# rev1_0.net
KiCad netlist of a schematic drawn in EAGLE
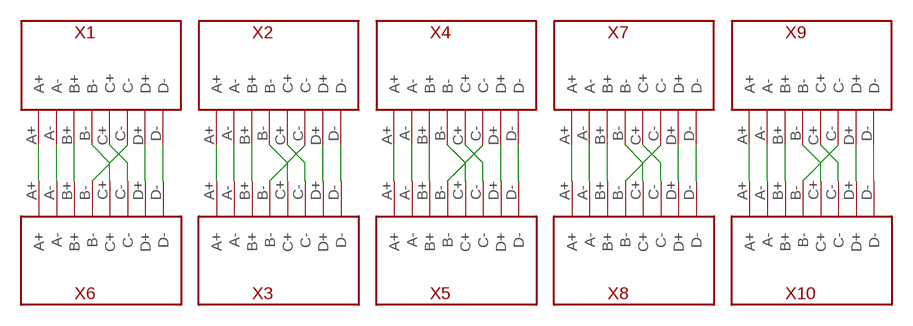
[diagram p0: schematic, sheet 1]

(export (version "E")
  (design (tool "Eeschema 10.0.6"))
  (components
    (comp (ref "X1")
      (value "ETHER_BRKOUT")
      (footprint "eagle-import:ETHER_BRKOUT")
      (libsource (lib "eagle-import") (part "ETHER_BRKOUT"))
    )
    (comp (ref "X2")
      (value "ETHER_BRKOUT")
      (footprint "eagle-import:ETHER_BRKOUT")
      (libsource (lib "eagle-import") (part "ETHER_BRKOUT"))
    )
    (comp (ref "X3")
      (value "ETHER_BRKOUT")
      (footprint "eagle-import:ETHER_BRKOUT")
      (libsource (lib "eagle-import") (part "ETHER_BRKOUT"))
    )
    (comp (ref "X4")
      (value "ETHER_BRKOUT")
      (footprint "eagle-import:ETHER_BRKOUT")
      (libsource (lib "eagle-import") (part "ETHER_BRKOUT"))
    )
    (comp (ref "X5")
      (value "ETHER_BRKOUT")
      (footprint "eagle-import:ETHER_BRKOUT")
      (libsource (lib "eagle-import") (part "ETHER_BRKOUT"))
    )
    (comp (ref "X6")
      (value "ETHER_BRKOUT")
      (footprint "eagle-import:ETHER_BRKOUT")
      (libsource (lib "eagle-import") (part "ETHER_BRKOUT"))
    )
    (comp (ref "X7")
      (value "ETHER_BRKOUT")
      (footprint "eagle-import:ETHER_BRKOUT")
      (libsource (lib "eagle-import") (part "ETHER_BRKOUT"))
    )
    (comp (ref "X8")
      (value "ETHER_BRKOUT")
      (footprint "eagle-import:ETHER_BRKOUT")
      (libsource (lib "eagle-import") (part "ETHER_BRKOUT"))
    )
    (comp (ref "X9")
      (value "ETHER_BRKOUT")
      (footprint "eagle-import:ETHER_BRKOUT")
      (libsource (lib "eagle-import") (part "ETHER_BRKOUT"))
    )
    (comp (ref "X10")
      (value "ETHER_BRKOUT")
      (footprint "eagle-import:ETHER_BRKOUT")
      (libsource (lib "eagle-import") (part "ETHER_BRKOUT"))
    )
  )
  (nets
    (net (code "1") (name "Net-(X1-PadA+)") (class "Default")
      (node (ref "X1") (pin "A+") (pinfunction "A+_A+") (pintype "bidirectional"))
      (node (ref "X6") (pin "A+") (pinfunction "A+_A+") (pintype "bidirectional"))
    )
    (net (code "2") (name "Net-(X1-PadA-)") (class "Default")
      (node (ref "X1") (pin "A-") (pinfunction "A-_A-") (pintype "bidirectional"))
      (node (ref "X6") (pin "A-") (pinfunction "A-_A-") (pintype "bidirectional"))
    )
    (net (code "3") (name "Net-(X1-PadB+)") (class "Default")
      (node (ref "X1") (pin "B+") (pinfunction "B+_B+") (pintype "bidirectional"))
      (node (ref "X6") (pin "B+") (pinfunction "B+_B+") (pintype "bidirectional"))
    )
    (net (code "4") (name "Net-(X1-PadB-)") (class "Default")
      (node (ref "X1") (pin "B-") (pinfunction "B-_B-") (pintype "bidirectional"))
      (node (ref "X6") (pin "C+") (pinfunction "C+_C+") (pintype "bidirectional"))
    )
    (net (code "5") (name "Net-(X1-PadC+)") (class "Default")
      (node (ref "X1") (pin "C+") (pinfunction "C+_C+") (pintype "bidirectional"))
      (node (ref "X6") (pin "C-") (pinfunction "C-_C-") (pintype "bidirectional"))
    )
    (net (code "6") (name "Net-(X1-PadC-)") (class "Default")
      (node (ref "X1") (pin "C-") (pinfunction "C-_C-") (pintype "bidirectional"))
      (node (ref "X6") (pin "B-") (pinfunction "B-_B-") (pintype "bidirectional"))
    )
    (net (code "7") (name "Net-(X1-PadD+)") (class "Default")
      (node (ref "X1") (pin "D+") (pinfunction "D+_D+") (pintype "bidirectional"))
      (node (ref "X6") (pin "D+") (pinfunction "D+_D+") (pintype "bidirectional"))
    )
    (net (code "8") (name "Net-(X1-PadD-)") (class "Default")
      (node (ref "X1") (pin "D-") (pinfunction "D-_D-") (pintype "bidirectional"))
      (node (ref "X6") (pin "D-") (pinfunction "D-_D-") (pintype "bidirectional"))
    )
    (net (code "9") (name "Net-(X2-PadA+)") (class "Default")
      (node (ref "X2") (pin "A+") (pinfunction "A+_A+") (pintype "bidirectional"))
      (node (ref "X3") (pin "A+") (pinfunction "A+_A+") (pintype "bidirectional"))
    )
    (net (code "10") (name "Net-(X2-PadA-)") (class "Default")
      (node (ref "X2") (pin "A-") (pinfunction "A-_A-") (pintype "bidirectional"))
      (node (ref "X3") (pin "A-") (pinfunction "A-_A-") (pintype "bidirectional"))
    )
    (net (code "11") (name "Net-(X2-PadB+)") (class "Default")
      (node (ref "X2") (pin "B+") (pinfunction "B+_B+") (pintype "bidirectional"))
      (node (ref "X3") (pin "B+") (pinfunction "B+_B+") (pintype "bidirectional"))
    )
    (net (code "12") (name "Net-(X2-PadB-)") (class "Default")
      (node (ref "X2") (pin "B-") (pinfunction "B-_B-") (pintype "bidirectional"))
      (node (ref "X3") (pin "C+") (pinfunction "C+_C+") (pintype "bidirectional"))
    )
    (net (code "13") (name "Net-(X2-PadC+)") (class "Default")
      (node (ref "X2") (pin "C+") (pinfunction "C+_C+") (pintype "bidirectional"))
      (node (ref "X3") (pin "C-") (pinfunction "C-_C-") (pintype "bidirectional"))
    )
    (net (code "14") (name "Net-(X2-PadC-)") (class "Default")
      (node (ref "X2") (pin "C-") (pinfunction "C-_C-") (pintype "bidirectional"))
      (node (ref "X3") (pin "B-") (pinfunction "B-_B-") (pintype "bidirectional"))
    )
    (net (code "15") (name "Net-(X2-PadD+)") (class "Default")
      (node (ref "X2") (pin "D+") (pinfunction "D+_D+") (pintype "bidirectional"))
      (node (ref "X3") (pin "D+") (pinfunction "D+_D+") (pintype "bidirectional"))
    )
    (net (code "16") (name "Net-(X2-PadD-)") (class "Default")
      (node (ref "X2") (pin "D-") (pinfunction "D-_D-") (pintype "bidirectional"))
      (node (ref "X3") (pin "D-") (pinfunction "D-_D-") (pintype "bidirectional"))
    )
    (net (code "17") (name "Net-(X4-PadA+)") (class "Default")
      (node (ref "X4") (pin "A+") (pinfunction "A+_A+") (pintype "bidirectional"))
      (node (ref "X5") (pin "A+") (pinfunction "A+_A+") (pintype "bidirectional"))
    )
    (net (code "18") (name "Net-(X4-PadA-)") (class "Default")
      (node (ref "X4") (pin "A-") (pinfunction "A-_A-") (pintype "bidirectional"))
      (node (ref "X5") (pin "A-") (pinfunction "A-_A-") (pintype "bidirectional"))
    )
    (net (code "19") (name "Net-(X4-PadB+)") (class "Default")
      (node (ref "X4") (pin "B+") (pinfunction "B+_B+") (pintype "bidirectional"))
      (node (ref "X5") (pin "B+") (pinfunction "B+_B+") (pintype "bidirectional"))
    )
    (net (code "20") (name "Net-(X4-PadB-)") (class "Default")
      (node (ref "X4") (pin "B-") (pinfunction "B-_B-") (pintype "bidirectional"))
      (node (ref "X5") (pin "C+") (pinfunction "C+_C+") (pintype "bidirectional"))
    )
    (net (code "21") (name "Net-(X4-PadC+)") (class "Default")
      (node (ref "X4") (pin "C+") (pinfunction "C+_C+") (pintype "bidirectional"))
      (node (ref "X5") (pin "C-") (pinfunction "C-_C-") (pintype "bidirectional"))
    )
    (net (code "22") (name "Net-(X4-PadC-)") (class "Default")
      (node (ref "X4") (pin "C-") (pinfunction "C-_C-") (pintype "bidirectional"))
      (node (ref "X5") (pin "B-") (pinfunction "B-_B-") (pintype "bidirectional"))
    )
    (net (code "23") (name "Net-(X4-PadD+)") (class "Default")
      (node (ref "X4") (pin "D+") (pinfunction "D+_D+") (pintype "bidirectional"))
      (node (ref "X5") (pin "D+") (pinfunction "D+_D+") (pintype "bidirectional"))
    )
    (net (code "24") (name "Net-(X4-PadD-)") (class "Default")
      (node (ref "X4") (pin "D-") (pinfunction "D-_D-") (pintype "bidirectional"))
      (node (ref "X5") (pin "D-") (pinfunction "D-_D-") (pintype "bidirectional"))
    )
    (net (code "25") (name "Net-(X7-PadA+)") (class "Default")
      (node (ref "X7") (pin "A+") (pinfunction "A+_A+") (pintype "bidirectional"))
      (node (ref "X8") (pin "A+") (pinfunction "A+_A+") (pintype "bidirectional"))
    )
    (net (code "26") (name "Net-(X7-PadA-)") (class "Default")
      (node (ref "X7") (pin "A-") (pinfunction "A-_A-") (pintype "bidirectional"))
      (node (ref "X8") (pin "A-") (pinfunction "A-_A-") (pintype "bidirectional"))
    )
    (net (code "27") (name "Net-(X7-PadB+)") (class "Default")
      (node (ref "X7") (pin "B+") (pinfunction "B+_B+") (pintype "bidirectional"))
      (node (ref "X8") (pin "B+") (pinfunction "B+_B+") (pintype "bidirectional"))
    )
    (net (code "28") (name "Net-(X7-PadB-)") (class "Default")
      (node (ref "X7") (pin "B-") (pinfunction "B-_B-") (pintype "bidirectional"))
      (node (ref "X8") (pin "C+") (pinfunction "C+_C+") (pintype "bidirectional"))
    )
    (net (code "29") (name "Net-(X7-PadC+)") (class "Default")
      (node (ref "X7") (pin "C+") (pinfunction "C+_C+") (pintype "bidirectional"))
      (node (ref "X8") (pin "C-") (pinfunction "C-_C-") (pintype "bidirectional"))
    )
    (net (code "30") (name "Net-(X7-PadC-)") (class "Default")
      (node (ref "X7") (pin "C-") (pinfunction "C-_C-") (pintype "bidirectional"))
      (node (ref "X8") (pin "B-") (pinfunction "B-_B-") (pintype "bidirectional"))
    )
    (net (code "31") (name "Net-(X7-PadD+)") (class "Default")
      (node (ref "X7") (pin "D+") (pinfunction "D+_D+") (pintype "bidirectional"))
      (node (ref "X8") (pin "D+") (pinfunction "D+_D+") (pintype "bidirectional"))
    )
    (net (code "32") (name "Net-(X7-PadD-)") (class "Default")
      (node (ref "X7") (pin "D-") (pinfunction "D-_D-") (pintype "bidirectional"))
      (node (ref "X8") (pin "D-") (pinfunction "D-_D-") (pintype "bidirectional"))
    )
    (net (code "33") (name "Net-(X10-PadA+)") (class "Default")
      (node (ref "X10") (pin "A+") (pinfunction "A+_A+") (pintype "bidirectional"))
      (node (ref "X9") (pin "A+") (pinfunction "A+_A+") (pintype "bidirectional"))
    )
    (net (code "34") (name "Net-(X10-PadA-)") (class "Default")
      (node (ref "X10") (pin "A-") (pinfunction "A-_A-") (pintype "bidirectional"))
      (node (ref "X9") (pin "A-") (pinfunction "A-_A-") (pintype "bidirectional"))
    )
    (net (code "35") (name "Net-(X10-PadB+)") (class "Default")
      (node (ref "X10") (pin "B+") (pinfunction "B+_B+") (pintype "bidirectional"))
      (node (ref "X9") (pin "B+") (pinfunction "B+_B+") (pintype "bidirectional"))
    )
    (net (code "36") (name "Net-(X10-PadB-)") (class "Default")
      (node (ref "X10") (pin "B-") (pinfunction "B-_B-") (pintype "bidirectional"))
      (node (ref "X9") (pin "C-") (pinfunction "C-_C-") (pintype "bidirectional"))
    )
    (net (code "37") (name "Net-(X10-PadC+)") (class "Default")
      (node (ref "X10") (pin "C+") (pinfunction "C+_C+") (pintype "bidirectional"))
      (node (ref "X9") (pin "B-") (pinfunction "B-_B-") (pintype "bidirectional"))
    )
    (net (code "38") (name "Net-(X10-PadC-)") (class "Default")
      (node (ref "X10") (pin "C-") (pinfunction "C-_C-") (pintype "bidirectional"))
      (node (ref "X9") (pin "C+") (pinfunction "C+_C+") (pintype "bidirectional"))
    )
    (net (code "39") (name "Net-(X10-PadD+)") (class "Default")
      (node (ref "X10") (pin "D+") (pinfunction "D+_D+") (pintype "bidirectional"))
      (node (ref "X9") (pin "D+") (pinfunction "D+_D+") (pintype "bidirectional"))
    )
    (net (code "40") (name "Net-(X10-PadD-)") (class "Default")
      (node (ref "X10") (pin "D-") (pinfunction "D-_D-") (pintype "bidirectional"))
      (node (ref "X9") (pin "D-") (pinfunction "D-_D-") (pintype "bidirectional"))
    )
  )
)
